# leds-logo.net
KiCad netlist of a schematic drawn in Altium Designer
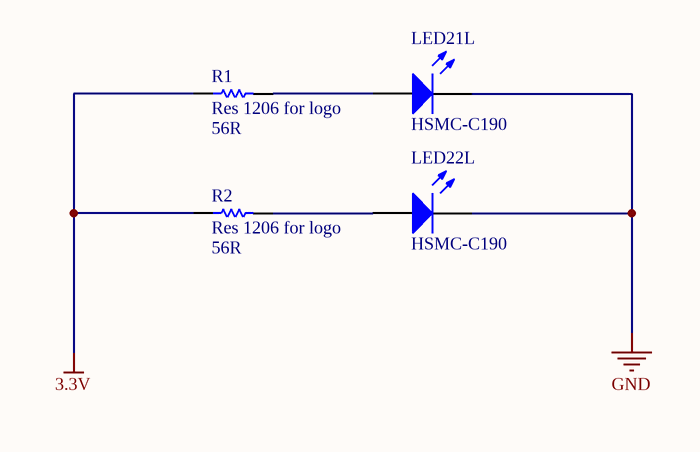
[diagram p0: leds-logo.SchDoc]

(export (version "E")
  (design (tool "Eeschema 10.0.6"))
  (components
    (comp (ref "LED21L")
      (value "HSMC-C190")
      (footprint "1.6X0.8X0.8")
      (description "High Performance Chip LED, Red")
      (fields (field (name "PUBLISHER") "Altium Limited"))
      (libsource (lib "Avago Optoelectronic LED") (part "HSMC-C190"))
    )
    (comp (ref "LED22L")
      (value "HSMC-C190")
      (footprint "1.6X0.8X0.8")
      (description "High Performance Chip LED, Red")
      (fields (field (name "PUBLISHER") "Altium Limited"))
      (libsource (lib "Avago Optoelectronic LED") (part "HSMC-C190"))
    )
    (comp (ref "R1")
      (value "Res 1206 for logo")
      (footprint "RESC1206(3216)_L")
      (description "180R 0.25W 5% 1206 (3216 Metric)  SMD")
      (fields
        (field (name "TOLERANCE") "5 %")
        (field (name "ALTIUM_VALUE") "56R")
        (field (name "POWER") "0.25 W")
      )
      (libsource (lib "Altium Content Vault") (part "CMP-1014-00056-1"))
    )
    (comp (ref "R2")
      (value "Res 1206 for logo")
      (footprint "RESC1206(3216)_L")
      (description "180R 0.25W 5% 1206 (3216 Metric)  SMD")
      (fields
        (field (name "TOLERANCE") "5 %")
        (field (name "ALTIUM_VALUE") "56R")
        (field (name "POWER") "0.25 W")
      )
      (libsource (lib "Altium Content Vault") (part "CMP-1014-00056-1"))
    )
  )
  (nets
    (net (code "1") (name "3.3V") (class "Default")
      (node (ref "R1") (pin "1") (pinfunction "1_1") (pintype "passive"))
      (node (ref "R2") (pin "1") (pinfunction "1_1") (pintype "passive"))
    )
    (net (code "2") (name "GND") (class "Default")
      (node (ref "LED21L") (pin "2") (pinfunction "K_2") (pintype "passive"))
      (node (ref "LED22L") (pin "2") (pinfunction "K_2") (pintype "passive"))
    )
    (net (code "3") (name "Net-(LED21L-A)") (class "Default")
      (node (ref "LED21L") (pin "1") (pinfunction "A_1") (pintype "passive"))
      (node (ref "R1") (pin "2") (pinfunction "2_2") (pintype "passive"))
    )
    (net (code "4") (name "Net-(LED22L-A)") (class "Default")
      (node (ref "LED22L") (pin "1") (pinfunction "A_1") (pintype "passive"))
      (node (ref "R2") (pin "2") (pinfunction "2_2") (pintype "passive"))
    )
  )
)
